# 001-top.net
KiCad netlist of a schematic drawn in EAGLE
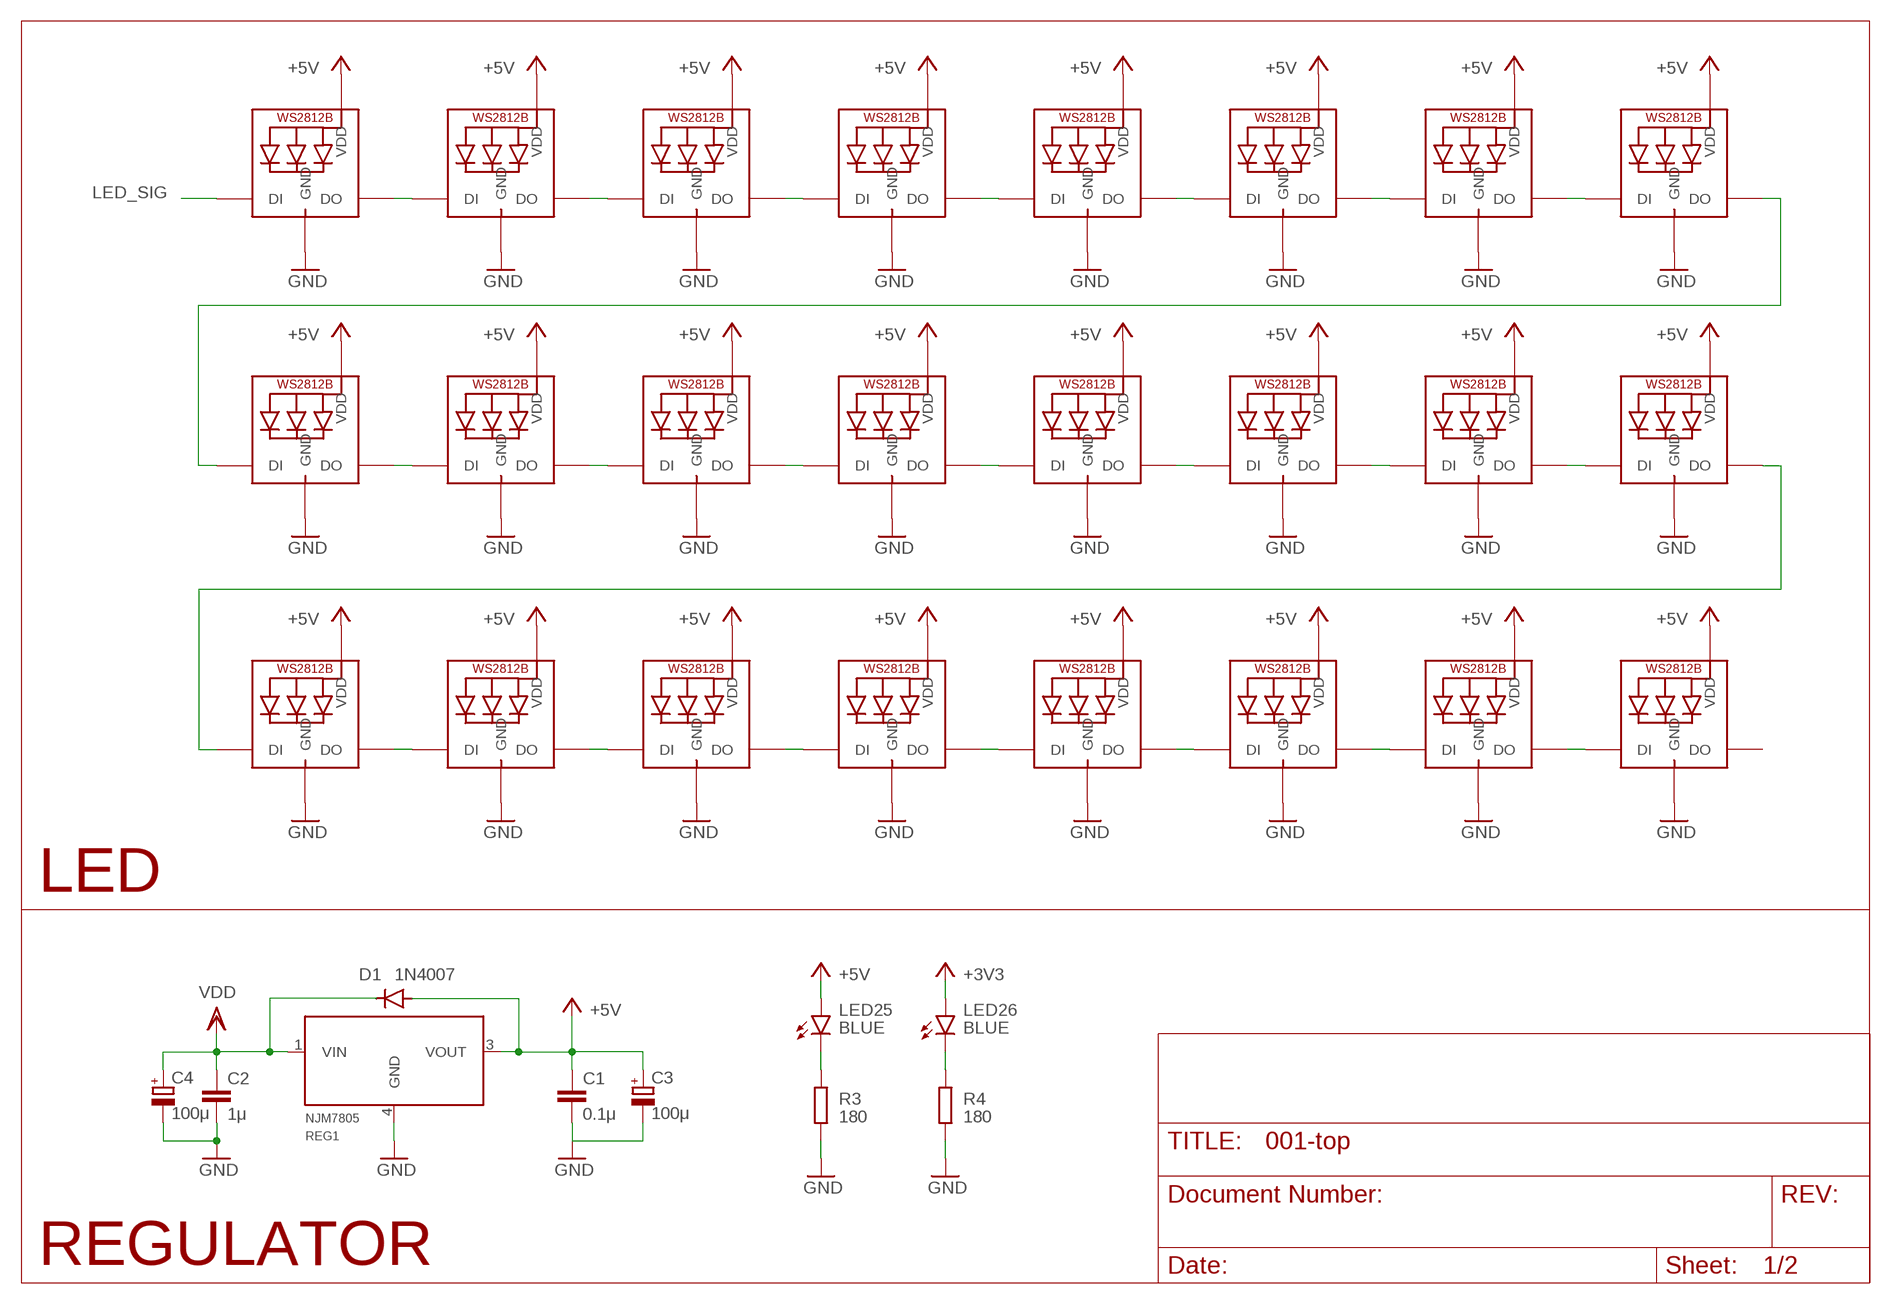
[diagram p0: schematic, sheet 1]
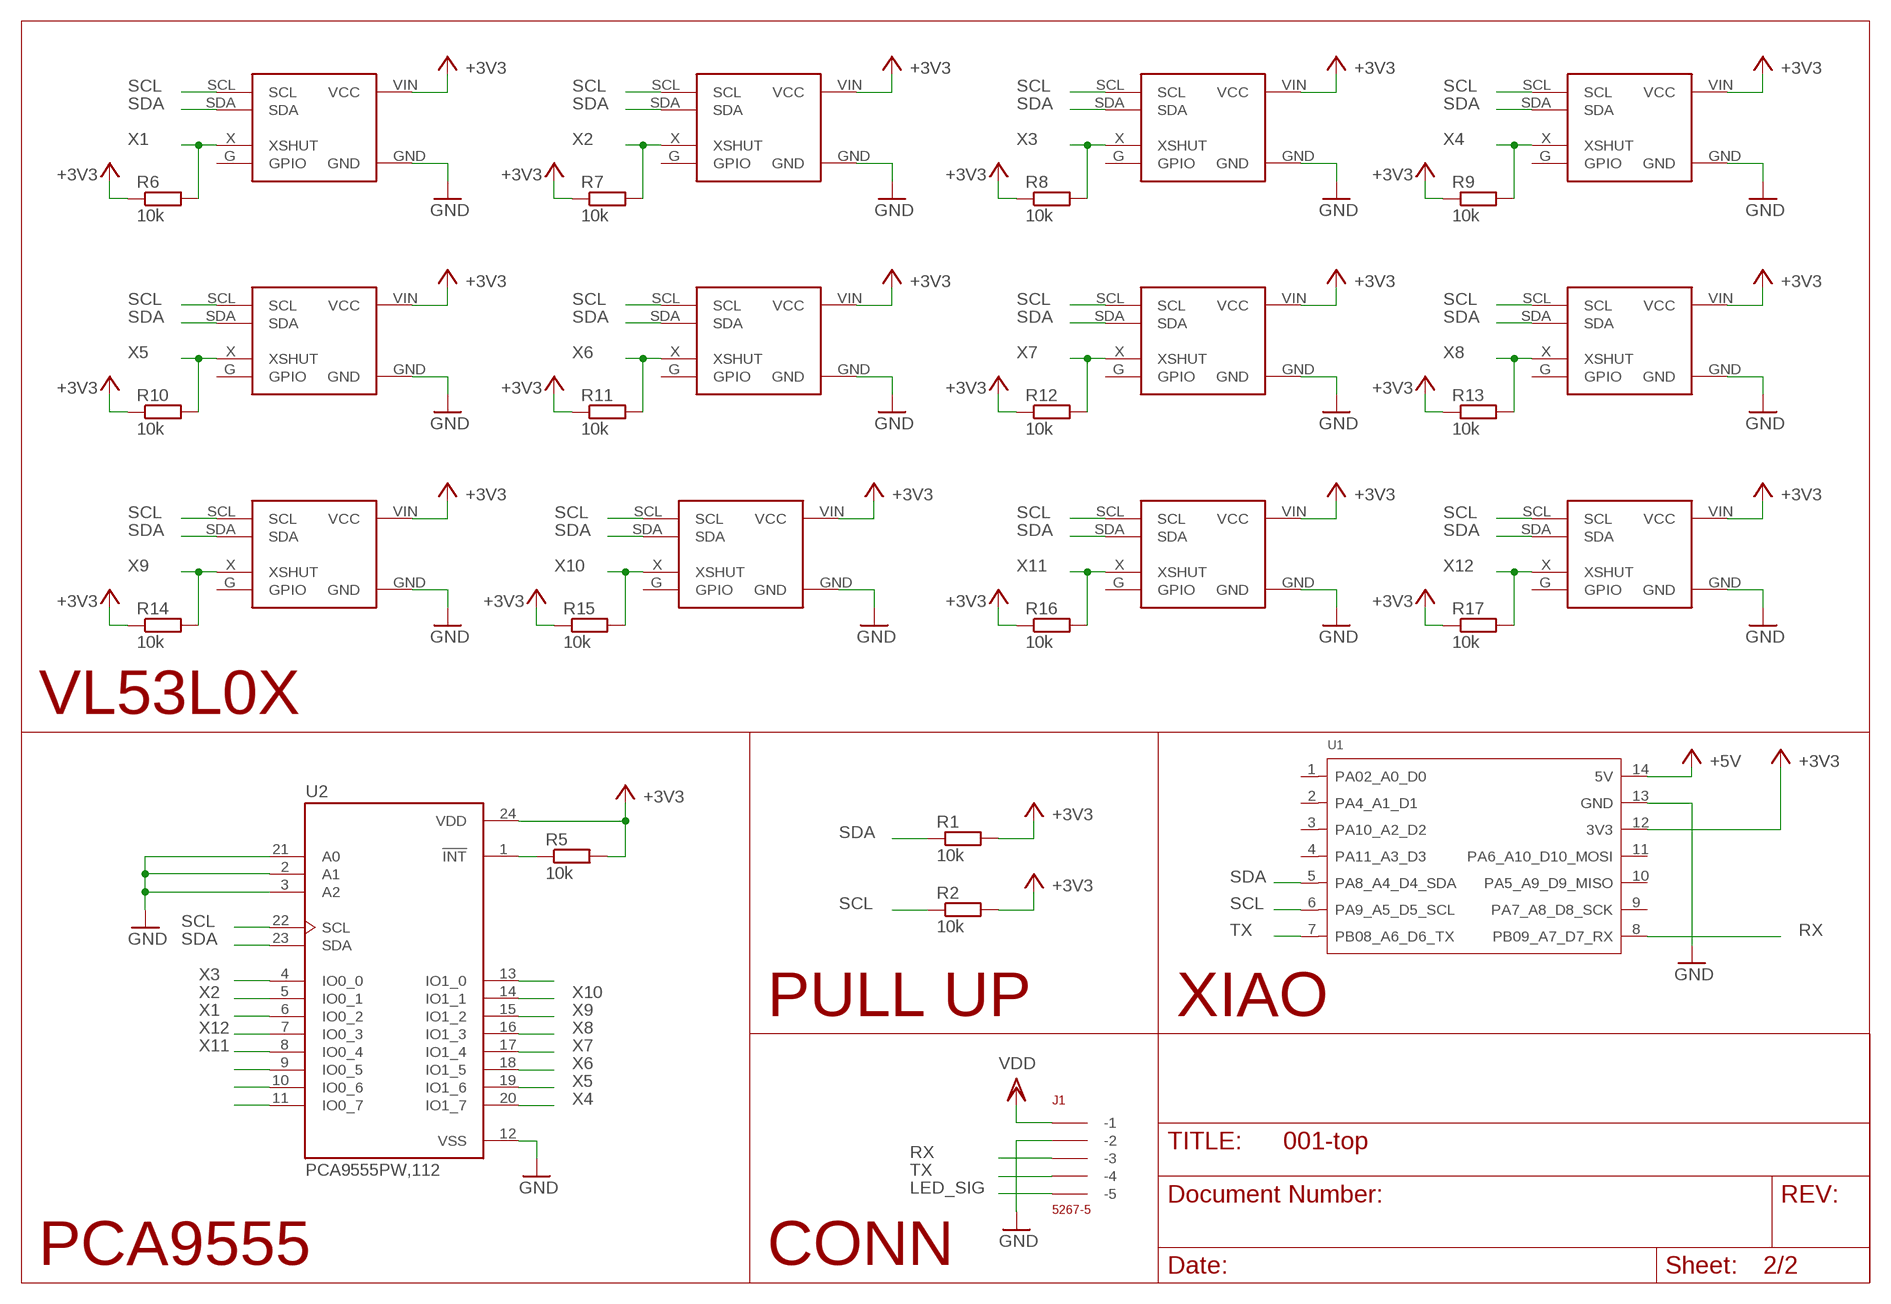
[diagram p1: schematic, sheet 2]

(export (version "E")
  (design (tool "Eeschema 10.0.6"))
  (components
    (comp (ref "C1")
      (value "0.1μ")
      (footprint "eagle-import:C0402")
      (libsource (lib "eagle-import") (part "C-EUC0402"))
    )
    (comp (ref "C2")
      (value "1μ")
      (footprint "eagle-import:C0402")
      (libsource (lib "eagle-import") (part "C-EUC0402"))
    )
    (comp (ref "C3")
      (value "100μ")
      (footprint "eagle-import:153CLV-0505")
      (libsource (lib "eagle-import") (part "CPOL-EU153CLV-0505"))
    )
    (comp (ref "C4")
      (value "100μ")
      (footprint "eagle-import:153CLV-0505")
      (libsource (lib "eagle-import") (part "CPOL-EU153CLV-0505"))
    )
    (comp (ref "D1")
      (value "1N4007")
      (footprint "eagle-import:SMA-DO214AC")
      (libsource (lib "eagle-import") (part "GF1"))
    )
    (comp (ref "LED1")
      (value "WS2812B_5050N")
      (footprint "eagle-import:WS2812B-NARROW")
      (libsource (lib "eagle-import") (part "WS2812B_5050N"))
    )
    (comp (ref "LED2")
      (value "WS2812B_5050N")
      (footprint "eagle-import:WS2812B-NARROW")
      (libsource (lib "eagle-import") (part "WS2812B_5050N"))
    )
    (comp (ref "LED3")
      (value "WS2812B_5050N")
      (footprint "eagle-import:WS2812B-NARROW")
      (libsource (lib "eagle-import") (part "WS2812B_5050N"))
    )
    (comp (ref "LED4")
      (value "WS2812B_5050N")
      (footprint "eagle-import:WS2812B-NARROW")
      (libsource (lib "eagle-import") (part "WS2812B_5050N"))
    )
    (comp (ref "LED5")
      (value "WS2812B_5050N")
      (footprint "eagle-import:WS2812B-NARROW")
      (libsource (lib "eagle-import") (part "WS2812B_5050N"))
    )
    (comp (ref "LED6")
      (value "WS2812B_5050N")
      (footprint "eagle-import:WS2812B-NARROW")
      (libsource (lib "eagle-import") (part "WS2812B_5050N"))
    )
    (comp (ref "LED7")
      (value "WS2812B_5050N")
      (footprint "eagle-import:WS2812B-NARROW")
      (libsource (lib "eagle-import") (part "WS2812B_5050N"))
    )
    (comp (ref "LED8")
      (value "WS2812B_5050N")
      (footprint "eagle-import:WS2812B-NARROW")
      (libsource (lib "eagle-import") (part "WS2812B_5050N"))
    )
    (comp (ref "LED9")
      (value "WS2812B_5050N")
      (footprint "eagle-import:WS2812B-NARROW")
      (libsource (lib "eagle-import") (part "WS2812B_5050N"))
    )
    (comp (ref "LED10")
      (value "WS2812B_5050N")
      (footprint "eagle-import:WS2812B-NARROW")
      (libsource (lib "eagle-import") (part "WS2812B_5050N"))
    )
    (comp (ref "LED11")
      (value "WS2812B_5050N")
      (footprint "eagle-import:WS2812B-NARROW")
      (libsource (lib "eagle-import") (part "WS2812B_5050N"))
    )
    (comp (ref "LED12")
      (value "WS2812B_5050N")
      (footprint "eagle-import:WS2812B-NARROW")
      (libsource (lib "eagle-import") (part "WS2812B_5050N"))
    )
    (comp (ref "LED13")
      (value "WS2812B_5050N")
      (footprint "eagle-import:WS2812B-NARROW")
      (libsource (lib "eagle-import") (part "WS2812B_5050N"))
    )
    (comp (ref "LED14")
      (value "WS2812B_5050N")
      (footprint "eagle-import:WS2812B-NARROW")
      (libsource (lib "eagle-import") (part "WS2812B_5050N"))
    )
    (comp (ref "LED15")
      (value "WS2812B_5050N")
      (footprint "eagle-import:WS2812B-NARROW")
      (libsource (lib "eagle-import") (part "WS2812B_5050N"))
    )
    (comp (ref "LED16")
      (value "WS2812B_5050N")
      (footprint "eagle-import:WS2812B-NARROW")
      (libsource (lib "eagle-import") (part "WS2812B_5050N"))
    )
    (comp (ref "LED17")
      (value "WS2812B_5050N")
      (footprint "eagle-import:WS2812B-NARROW")
      (libsource (lib "eagle-import") (part "WS2812B_5050N"))
    )
    (comp (ref "LED18")
      (value "WS2812B_5050N")
      (footprint "eagle-import:WS2812B-NARROW")
      (libsource (lib "eagle-import") (part "WS2812B_5050N"))
    )
    (comp (ref "LED19")
      (value "WS2812B_5050N")
      (footprint "eagle-import:WS2812B-NARROW")
      (libsource (lib "eagle-import") (part "WS2812B_5050N"))
    )
    (comp (ref "LED20")
      (value "WS2812B_5050N")
      (footprint "eagle-import:WS2812B-NARROW")
      (libsource (lib "eagle-import") (part "WS2812B_5050N"))
    )
    (comp (ref "LED21")
      (value "WS2812B_5050N")
      (footprint "eagle-import:WS2812B-NARROW")
      (libsource (lib "eagle-import") (part "WS2812B_5050N"))
    )
    (comp (ref "LED22")
      (value "WS2812B_5050N")
      (footprint "eagle-import:WS2812B-NARROW")
      (libsource (lib "eagle-import") (part "WS2812B_5050N"))
    )
    (comp (ref "LED23")
      (value "WS2812B_5050N")
      (footprint "eagle-import:WS2812B-NARROW")
      (libsource (lib "eagle-import") (part "WS2812B_5050N"))
    )
    (comp (ref "LED24")
      (value "WS2812B_5050N")
      (footprint "eagle-import:WS2812B-NARROW")
      (libsource (lib "eagle-import") (part "WS2812B_5050N"))
    )
    (comp (ref "LED25")
      (value "BLUE")
      (footprint "eagle-import:SML0603")
      (libsource (lib "eagle-import") (part "LEDSML0603"))
    )
    (comp (ref "LED26")
      (value "BLUE")
      (footprint "eagle-import:SML0603")
      (libsource (lib "eagle-import") (part "LEDSML0603"))
    )
    (comp (ref "R3")
      (value "180")
      (footprint "eagle-import:R0402")
      (libsource (lib "eagle-import") (part "R-EU_R0402"))
    )
    (comp (ref "R4")
      (value "180")
      (footprint "eagle-import:R0402")
      (libsource (lib "eagle-import") (part "R-EU_R0402"))
    )
    (comp (ref "REG1")
      (value "NJM7805")
      (footprint "eagle-import:MYPARTS_D-PAK_TO252AA")
      (libsource (lib "eagle-import") (part "MYPARTS_NJM7800S-REGULATOR"))
    )
    (comp (ref "J1")
      (value "5267-5")
      (footprint "eagle-import:5267-5")
      (libsource (lib "eagle-import") (part "5267-5"))
    )
    (comp (ref "R1")
      (value "10k")
      (footprint "eagle-import:R0402")
      (libsource (lib "eagle-import") (part "R-EU_R0402"))
    )
    (comp (ref "R2")
      (value "10k")
      (footprint "eagle-import:R0402")
      (libsource (lib "eagle-import") (part "R-EU_R0402"))
    )
    (comp (ref "R5")
      (value "10k")
      (footprint "eagle-import:R0402")
      (libsource (lib "eagle-import") (part "R-EU_R0402"))
    )
    (comp (ref "R6")
      (value "10k")
      (footprint "eagle-import:R0402")
      (libsource (lib "eagle-import") (part "R-EU_R0402"))
    )
    (comp (ref "R7")
      (value "10k")
      (footprint "eagle-import:R0402")
      (libsource (lib "eagle-import") (part "R-EU_R0402"))
    )
    (comp (ref "R8")
      (value "10k")
      (footprint "eagle-import:R0402")
      (libsource (lib "eagle-import") (part "R-EU_R0402"))
    )
    (comp (ref "R9")
      (value "10k")
      (footprint "eagle-import:R0402")
      (libsource (lib "eagle-import") (part "R-EU_R0402"))
    )
    (comp (ref "R10")
      (value "10k")
      (footprint "eagle-import:R0402")
      (libsource (lib "eagle-import") (part "R-EU_R0402"))
    )
    (comp (ref "R11")
      (value "10k")
      (footprint "eagle-import:R0402")
      (libsource (lib "eagle-import") (part "R-EU_R0402"))
    )
    (comp (ref "R12")
      (value "10k")
      (footprint "eagle-import:R0402")
      (libsource (lib "eagle-import") (part "R-EU_R0402"))
    )
    (comp (ref "R13")
      (value "10k")
      (footprint "eagle-import:R0402")
      (libsource (lib "eagle-import") (part "R-EU_R0402"))
    )
    (comp (ref "R14")
      (value "10k")
      (footprint "eagle-import:R0402")
      (libsource (lib "eagle-import") (part "R-EU_R0402"))
    )
    (comp (ref "R15")
      (value "10k")
      (footprint "eagle-import:R0402")
      (libsource (lib "eagle-import") (part "R-EU_R0402"))
    )
    (comp (ref "R16")
      (value "10k")
      (footprint "eagle-import:R0402")
      (libsource (lib "eagle-import") (part "R-EU_R0402"))
    )
    (comp (ref "R17")
      (value "10k")
      (footprint "eagle-import:R0402")
      (libsource (lib "eagle-import") (part "R-EU_R0402"))
    )
    (comp (ref "U1")
      (value "MOUDLE-SEEEDUINO-XIAO")
      (footprint "eagle-import:MOUDLE14P-2.54-21X17.8MM")
      (libsource (lib "eagle-import") (part "MOUDLE-SEEEDUINO-XIAO"))
    )
    (comp (ref "U2")
      (value "PCA9555PW,112")
      (footprint "eagle-import:SOP65P640X110-24N")
      (fields (field (name "MF") "NXP Semiconductors"))
      (libsource (lib "eagle-import") (part "PCA9555PW,112"))
    )
    (comp (ref "VL1")
      (value "VL53L0X")
      (footprint "eagle-import:1X04")
      (libsource (lib "eagle-import") (part "VL53L0X"))
    )
    (comp (ref "VL2")
      (value "VL53L0X")
      (footprint "eagle-import:1X04")
      (libsource (lib "eagle-import") (part "VL53L0X"))
    )
    (comp (ref "VL3")
      (value "VL53L0X")
      (footprint "eagle-import:1X04")
      (libsource (lib "eagle-import") (part "VL53L0X"))
    )
    (comp (ref "VL4")
      (value "VL53L0X")
      (footprint "eagle-import:1X04")
      (libsource (lib "eagle-import") (part "VL53L0X"))
    )
    (comp (ref "VL5")
      (value "VL53L0X")
      (footprint "eagle-import:1X04")
      (libsource (lib "eagle-import") (part "VL53L0X"))
    )
    (comp (ref "VL6")
      (value "VL53L0X")
      (footprint "eagle-import:1X04")
      (libsource (lib "eagle-import") (part "VL53L0X"))
    )
    (comp (ref "VL7")
      (value "VL53L0X")
      (footprint "eagle-import:1X04")
      (libsource (lib "eagle-import") (part "VL53L0X"))
    )
    (comp (ref "VL8")
      (value "VL53L0X")
      (footprint "eagle-import:1X04")
      (libsource (lib "eagle-import") (part "VL53L0X"))
    )
    (comp (ref "VL9")
      (value "VL53L0X")
      (footprint "eagle-import:1X04")
      (libsource (lib "eagle-import") (part "VL53L0X"))
    )
    (comp (ref "VL10")
      (value "VL53L0X")
      (footprint "eagle-import:1X04")
      (libsource (lib "eagle-import") (part "VL53L0X"))
    )
    (comp (ref "VL11")
      (value "VL53L0X")
      (footprint "eagle-import:1X04")
      (libsource (lib "eagle-import") (part "VL53L0X"))
    )
    (comp (ref "VL12")
      (value "VL53L0X")
      (footprint "eagle-import:1X04")
      (libsource (lib "eagle-import") (part "VL53L0X"))
    )
  )
  (nets
    (net (code "1") (name "+3V3") (class "Default")
      (node (ref "LED26") (pin "A") (pinfunction "A_A") (pintype "passive"))
      (node (ref "R1") (pin "2") (pinfunction "2_2") (pintype "passive"))
      (node (ref "R10") (pin "1") (pinfunction "1_1") (pintype "passive"))
      (node (ref "R11") (pin "1") (pinfunction "1_1") (pintype "passive"))
      (node (ref "R12") (pin "1") (pinfunction "1_1") (pintype "passive"))
      (node (ref "R13") (pin "1") (pinfunction "1_1") (pintype "passive"))
      (node (ref "R14") (pin "1") (pinfunction "1_1") (pintype "passive"))
      (node (ref "R15") (pin "1") (pinfunction "1_1") (pintype "passive"))
      (node (ref "R16") (pin "1") (pinfunction "1_1") (pintype "passive"))
      (node (ref "R17") (pin "1") (pinfunction "1_1") (pintype "passive"))
      (node (ref "R2") (pin "2") (pinfunction "2_2") (pintype "passive"))
      (node (ref "R5") (pin "2") (pinfunction "2_2") (pintype "passive"))
      (node (ref "R6") (pin "1") (pinfunction "1_1") (pintype "passive"))
      (node (ref "R7") (pin "1") (pinfunction "1_1") (pintype "passive"))
      (node (ref "R8") (pin "1") (pinfunction "1_1") (pintype "passive"))
      (node (ref "R9") (pin "1") (pinfunction "1_1") (pintype "passive"))
      (node (ref "U1") (pin "12") (pinfunction "3V3_12") (pintype "bidirectional"))
      (node (ref "U2") (pin "24") (pinfunction "VDD_24") (pintype "power_in"))
      (node (ref "VL1") (pin "VIN") (pinfunction "VCC_VIN") (pintype "bidirectional"))
      (node (ref "VL10") (pin "VIN") (pinfunction "VCC_VIN") (pintype "bidirectional"))
      (node (ref "VL11") (pin "VIN") (pinfunction "VCC_VIN") (pintype "bidirectional"))
      (node (ref "VL12") (pin "VIN") (pinfunction "VCC_VIN") (pintype "bidirectional"))
      (node (ref "VL2") (pin "VIN") (pinfunction "VCC_VIN") (pintype "bidirectional"))
      (node (ref "VL3") (pin "VIN") (pinfunction "VCC_VIN") (pintype "bidirectional"))
      (node (ref "VL4") (pin "VIN") (pinfunction "VCC_VIN") (pintype "bidirectional"))
      (node (ref "VL5") (pin "VIN") (pinfunction "VCC_VIN") (pintype "bidirectional"))
      (node (ref "VL6") (pin "VIN") (pinfunction "VCC_VIN") (pintype "bidirectional"))
      (node (ref "VL7") (pin "VIN") (pinfunction "VCC_VIN") (pintype "bidirectional"))
      (node (ref "VL8") (pin "VIN") (pinfunction "VCC_VIN") (pintype "bidirectional"))
      (node (ref "VL9") (pin "VIN") (pinfunction "VCC_VIN") (pintype "bidirectional"))
    )
    (net (code "2") (name "+5V") (class "Default")
      (node (ref "C1") (pin "1") (pinfunction "1_1") (pintype "passive"))
      (node (ref "C3") (pin "+") (pinfunction "+_+") (pintype "passive"))
      (node (ref "D1") (pin "A") (pinfunction "A_A") (pintype "passive"))
      (node (ref "LED1") (pin "1-VDD") (pinfunction "VDD_1-VDD") (pintype "power_in"))
      (node (ref "LED10") (pin "1-VDD") (pinfunction "VDD_1-VDD") (pintype "power_in"))
      (node (ref "LED11") (pin "1-VDD") (pinfunction "VDD_1-VDD") (pintype "power_in"))
      (node (ref "LED12") (pin "1-VDD") (pinfunction "VDD_1-VDD") (pintype "power_in"))
      (node (ref "LED13") (pin "1-VDD") (pinfunction "VDD_1-VDD") (pintype "power_in"))
      (node (ref "LED14") (pin "1-VDD") (pinfunction "VDD_1-VDD") (pintype "power_in"))
      (node (ref "LED15") (pin "1-VDD") (pinfunction "VDD_1-VDD") (pintype "power_in"))
      (node (ref "LED16") (pin "1-VDD") (pinfunction "VDD_1-VDD") (pintype "power_in"))
      (node (ref "LED17") (pin "1-VDD") (pinfunction "VDD_1-VDD") (pintype "power_in"))
      (node (ref "LED18") (pin "1-VDD") (pinfunction "VDD_1-VDD") (pintype "power_in"))
      (node (ref "LED19") (pin "1-VDD") (pinfunction "VDD_1-VDD") (pintype "power_in"))
      (node (ref "LED2") (pin "1-VDD") (pinfunction "VDD_1-VDD") (pintype "power_in"))
      (node (ref "LED20") (pin "1-VDD") (pinfunction "VDD_1-VDD") (pintype "power_in"))
      (node (ref "LED21") (pin "1-VDD") (pinfunction "VDD_1-VDD") (pintype "power_in"))
      (node (ref "LED22") (pin "1-VDD") (pinfunction "VDD_1-VDD") (pintype "power_in"))
      (node (ref "LED23") (pin "1-VDD") (pinfunction "VDD_1-VDD") (pintype "power_in"))
      (node (ref "LED24") (pin "1-VDD") (pinfunction "VDD_1-VDD") (pintype "power_in"))
      (node (ref "LED25") (pin "A") (pinfunction "A_A") (pintype "passive"))
      (node (ref "LED3") (pin "1-VDD") (pinfunction "VDD_1-VDD") (pintype "power_in"))
      (node (ref "LED4") (pin "1-VDD") (pinfunction "VDD_1-VDD") (pintype "power_in"))
      (node (ref "LED5") (pin "1-VDD") (pinfunction "VDD_1-VDD") (pintype "power_in"))
      (node (ref "LED6") (pin "1-VDD") (pinfunction "VDD_1-VDD") (pintype "power_in"))
      (node (ref "LED7") (pin "1-VDD") (pinfunction "VDD_1-VDD") (pintype "power_in"))
      (node (ref "LED8") (pin "1-VDD") (pinfunction "VDD_1-VDD") (pintype "power_in"))
      (node (ref "LED9") (pin "1-VDD") (pinfunction "VDD_1-VDD") (pintype "power_in"))
      (node (ref "REG1") (pin "3") (pinfunction "VOUT_3") (pintype "passive"))
      (node (ref "U1") (pin "14") (pinfunction "5V_14") (pintype "bidirectional"))
    )
    (net (code "3") (name "GND") (class "Default")
      (node (ref "C1") (pin "2") (pinfunction "2_2") (pintype "passive"))
      (node (ref "C2") (pin "2") (pinfunction "2_2") (pintype "passive"))
      (node (ref "C3") (pin "-") (pinfunction "-_-") (pintype "passive"))
      (node (ref "C4") (pin "-") (pinfunction "-_-") (pintype "passive"))
      (node (ref "J1") (pin "P$2") (pinfunction "-2_P$2") (pintype "bidirectional"))
      (node (ref "LED1") (pin "3-GND") (pinfunction "GND_3-GND") (pintype "power_in"))
      (node (ref "LED10") (pin "3-GND") (pinfunction "GND_3-GND") (pintype "power_in"))
      (node (ref "LED11") (pin "3-GND") (pinfunction "GND_3-GND") (pintype "power_in"))
      (node (ref "LED12") (pin "3-GND") (pinfunction "GND_3-GND") (pintype "power_in"))
      (node (ref "LED13") (pin "3-GND") (pinfunction "GND_3-GND") (pintype "power_in"))
      (node (ref "LED14") (pin "3-GND") (pinfunction "GND_3-GND") (pintype "power_in"))
      (node (ref "LED15") (pin "3-GND") (pinfunction "GND_3-GND") (pintype "power_in"))
      (node (ref "LED16") (pin "3-GND") (pinfunction "GND_3-GND") (pintype "power_in"))
      (node (ref "LED17") (pin "3-GND") (pinfunction "GND_3-GND") (pintype "power_in"))
      (node (ref "LED18") (pin "3-GND") (pinfunction "GND_3-GND") (pintype "power_in"))
      (node (ref "LED19") (pin "3-GND") (pinfunction "GND_3-GND") (pintype "power_in"))
      (node (ref "LED2") (pin "3-GND") (pinfunction "GND_3-GND") (pintype "power_in"))
      (node (ref "LED20") (pin "3-GND") (pinfunction "GND_3-GND") (pintype "power_in"))
      (node (ref "LED21") (pin "3-GND") (pinfunction "GND_3-GND") (pintype "power_in"))
      (node (ref "LED22") (pin "3-GND") (pinfunction "GND_3-GND") (pintype "power_in"))
      (node (ref "LED23") (pin "3-GND") (pinfunction "GND_3-GND") (pintype "power_in"))
      (node (ref "LED24") (pin "3-GND") (pinfunction "GND_3-GND") (pintype "power_in"))
      (node (ref "LED3") (pin "3-GND") (pinfunction "GND_3-GND") (pintype "power_in"))
      (node (ref "LED4") (pin "3-GND") (pinfunction "GND_3-GND") (pintype "power_in"))
      (node (ref "LED5") (pin "3-GND") (pinfunction "GND_3-GND") (pintype "power_in"))
      (node (ref "LED6") (pin "3-GND") (pinfunction "GND_3-GND") (pintype "power_in"))
      (node (ref "LED7") (pin "3-GND") (pinfunction "GND_3-GND") (pintype "power_in"))
      (node (ref "LED8") (pin "3-GND") (pinfunction "GND_3-GND") (pintype "power_in"))
      (node (ref "LED9") (pin "3-GND") (pinfunction "GND_3-GND") (pintype "power_in"))
      (node (ref "R3") (pin "2") (pinfunction "2_2") (pintype "passive"))
      (node (ref "R4") (pin "2") (pinfunction "2_2") (pintype "passive"))
      (node (ref "REG1") (pin "4") (pinfunction "GND_4") (pintype "passive"))
      (node (ref "U1") (pin "13") (pinfunction "GND_13") (pintype "bidirectional"))
      (node (ref "U2") (pin "12") (pinfunction "VSS_12") (pintype "power_in"))
      (node (ref "U2") (pin "2") (pinfunction "A1_2") (pintype "input"))
      (node (ref "U2") (pin "21") (pinfunction "A0_21") (pintype "input"))
      (node (ref "U2") (pin "3") (pinfunction "A2_3") (pintype "input"))
      (node (ref "VL1") (pin "GND") (pinfunction "GND_GND") (pintype "bidirectional"))
      (node (ref "VL10") (pin "GND") (pinfunction "GND_GND") (pintype "bidirectional"))
      (node (ref "VL11") (pin "GND") (pinfunction "GND_GND") (pintype "bidirectional"))
      (node (ref "VL12") (pin "GND") (pinfunction "GND_GND") (pintype "bidirectional"))
      (node (ref "VL2") (pin "GND") (pinfunction "GND_GND") (pintype "bidirectional"))
      (node (ref "VL3") (pin "GND") (pinfunction "GND_GND") (pintype "bidirectional"))
      (node (ref "VL4") (pin "GND") (pinfunction "GND_GND") (pintype "bidirectional"))
      (node (ref "VL5") (pin "GND") (pinfunction "GND_GND") (pintype "bidirectional"))
      (node (ref "VL6") (pin "GND") (pinfunction "GND_GND") (pintype "bidirectional"))
      (node (ref "VL7") (pin "GND") (pinfunction "GND_GND") (pintype "bidirectional"))
      (node (ref "VL8") (pin "GND") (pinfunction "GND_GND") (pintype "bidirectional"))
      (node (ref "VL9") (pin "GND") (pinfunction "GND_GND") (pintype "bidirectional"))
    )
    (net (code "4") (name "LED_SIG") (class "Default")
      (node (ref "J1") (pin "P$5") (pinfunction "-5_P$5") (pintype "bidirectional"))
      (node (ref "LED1") (pin "4-DIN") (pinfunction "DI_4-DIN") (pintype "input"))
    )
    (net (code "5") (name "Net-(LED1-DO)") (class "Default")
      (node (ref "LED1") (pin "2-DOUT") (pinfunction "DO_2-DOUT") (pintype "output"))
      (node (ref "LED2") (pin "4-DIN") (pinfunction "DI_4-DIN") (pintype "input"))
    )
    (net (code "6") (name "Net-(LED2-DO)") (class "Default")
      (node (ref "LED2") (pin "2-DOUT") (pinfunction "DO_2-DOUT") (pintype "output"))
      (node (ref "LED3") (pin "4-DIN") (pinfunction "DI_4-DIN") (pintype "input"))
    )
    (net (code "7") (name "Net-(LED3-DO)") (class "Default")
      (node (ref "LED3") (pin "2-DOUT") (pinfunction "DO_2-DOUT") (pintype "output"))
      (node (ref "LED4") (pin "4-DIN") (pinfunction "DI_4-DIN") (pintype "input"))
    )
    (net (code "8") (name "Net-(LED4-DO)") (class "Default")
      (node (ref "LED4") (pin "2-DOUT") (pinfunction "DO_2-DOUT") (pintype "output"))
      (node (ref "LED5") (pin "4-DIN") (pinfunction "DI_4-DIN") (pintype "input"))
    )
    (net (code "9") (name "Net-(LED5-DO)") (class "Default")
      (node (ref "LED5") (pin "2-DOUT") (pinfunction "DO_2-DOUT") (pintype "output"))
      (node (ref "LED6") (pin "4-DIN") (pinfunction "DI_4-DIN") (pintype "input"))
    )
    (net (code "10") (name "Net-(LED6-DO)") (class "Default")
      (node (ref "LED6") (pin "2-DOUT") (pinfunction "DO_2-DOUT") (pintype "output"))
      (node (ref "LED7") (pin "4-DIN") (pinfunction "DI_4-DIN") (pintype "input"))
    )
    (net (code "11") (name "Net-(LED7-DO)") (class "Default")
      (node (ref "LED7") (pin "2-DOUT") (pinfunction "DO_2-DOUT") (pintype "output"))
      (node (ref "LED8") (pin "4-DIN") (pinfunction "DI_4-DIN") (pintype "input"))
    )
    (net (code "12") (name "Net-(LED8-DO)") (class "Default")
      (node (ref "LED8") (pin "2-DOUT") (pinfunction "DO_2-DOUT") (pintype "output"))
      (node (ref "LED9") (pin "4-DIN") (pinfunction "DI_4-DIN") (pintype "input"))
    )
    (net (code "13") (name "Net-(LED10-DI)") (class "Default")
      (node (ref "LED10") (pin "4-DIN") (pinfunction "DI_4-DIN") (pintype "input"))
      (node (ref "LED9") (pin "2-DOUT") (pinfunction "DO_2-DOUT") (pintype "output"))
    )
    (net (code "14") (name "Net-(LED10-DO)") (class "Default")
      (node (ref "LED10") (pin "2-DOUT") (pinfunction "DO_2-DOUT") (pintype "output"))
      (node (ref "LED11") (pin "4-DIN") (pinfunction "DI_4-DIN") (pintype "input"))
    )
    (net (code "15") (name "Net-(LED11-DO)") (class "Default")
      (node (ref "LED11") (pin "2-DOUT") (pinfunction "DO_2-DOUT") (pintype "output"))
      (node (ref "LED12") (pin "4-DIN") (pinfunction "DI_4-DIN") (pintype "input"))
    )
    (net (code "16") (name "Net-(LED12-DO)") (class "Default")
      (node (ref "LED12") (pin "2-DOUT") (pinfunction "DO_2-DOUT") (pintype "output"))
      (node (ref "LED13") (pin "4-DIN") (pinfunction "DI_4-DIN") (pintype "input"))
    )
    (net (code "17") (name "Net-(LED13-DO)") (class "Default")
      (node (ref "LED13") (pin "2-DOUT") (pinfunction "DO_2-DOUT") (pintype "output"))
      (node (ref "LED14") (pin "4-DIN") (pinfunction "DI_4-DIN") (pintype "input"))
    )
    (net (code "18") (name "Net-(LED14-DO)") (class "Default")
      (node (ref "LED14") (pin "2-DOUT") (pinfunction "DO_2-DOUT") (pintype "output"))
      (node (ref "LED15") (pin "4-DIN") (pinfunction "DI_4-DIN") (pintype "input"))
    )
    (net (code "19") (name "Net-(LED15-DO)") (class "Default")
      (node (ref "LED15") (pin "2-DOUT") (pinfunction "DO_2-DOUT") (pintype "output"))
      (node (ref "LED16") (pin "4-DIN") (pinfunction "DI_4-DIN") (pintype "input"))
    )
    (net (code "20") (name "Net-(LED16-DO)") (class "Default")
      (node (ref "LED16") (pin "2-DOUT") (pinfunction "DO_2-DOUT") (pintype "output"))
      (node (ref "LED17") (pin "4-DIN") (pinfunction "DI_4-DIN") (pintype "input"))
    )
    (net (code "21") (name "Net-(LED17-DO)") (class "Default")
      (node (ref "LED17") (pin "2-DOUT") (pinfunction "DO_2-DOUT") (pintype "output"))
      (node (ref "LED18") (pin "4-DIN") (pinfunction "DI_4-DIN") (pintype "input"))
    )
    (net (code "22") (name "Net-(LED18-DO)") (class "Default")
      (node (ref "LED18") (pin "2-DOUT") (pinfunction "DO_2-DOUT") (pintype "output"))
      (node (ref "LED19") (pin "4-DIN") (pinfunction "DI_4-DIN") (pintype "input"))
    )
    (net (code "23") (name "Net-(LED19-DO)") (class "Default")
      (node (ref "LED19") (pin "2-DOUT") (pinfunction "DO_2-DOUT") (pintype "output"))
      (node (ref "LED20") (pin "4-DIN") (pinfunction "DI_4-DIN") (pintype "input"))
    )
    (net (code "24") (name "Net-(LED20-DO)") (class "Default")
      (node (ref "LED20") (pin "2-DOUT") (pinfunction "DO_2-DOUT") (pintype "output"))
      (node (ref "LED21") (pin "4-DIN") (pinfunction "DI_4-DIN") (pintype "input"))
    )
    (net (code "25") (name "Net-(LED21-DO)") (class "Default")
      (node (ref "LED21") (pin "2-DOUT") (pinfunction "DO_2-DOUT") (pintype "output"))
      (node (ref "LED22") (pin "4-DIN") (pinfunction "DI_4-DIN") (pintype "input"))
    )
    (net (code "26") (name "Net-(LED22-DO)") (class "Default")
      (node (ref "LED22") (pin "2-DOUT") (pinfunction "DO_2-DOUT") (pintype "output"))
      (node (ref "LED23") (pin "4-DIN") (pinfunction "DI_4-DIN") (pintype "input"))
    )
    (net (code "27") (name "Net-(LED23-DO)") (class "Default")
      (node (ref "LED23") (pin "2-DOUT") (pinfunction "DO_2-DOUT") (pintype "output"))
      (node (ref "LED24") (pin "4-DIN") (pinfunction "DI_4-DIN") (pintype "input"))
    )
    (net (code "28") (name "Net-(LED25-PadC)") (class "Default")
      (node (ref "LED25") (pin "C") (pinfunction "C_C") (pintype "passive"))
      (node (ref "R3") (pin "1") (pinfunction "1_1") (pintype "passive"))
    )
    (net (code "29") (name "Net-(LED26-PadC)") (class "Default")
      (node (ref "LED26") (pin "C") (pinfunction "C_C") (pintype "passive"))
      (node (ref "R4") (pin "1") (pinfunction "1_1") (pintype "passive"))
    )
    (net (code "30") (name "Net-(U2-~{INT})") (class "Default")
      (node (ref "R5") (pin "1") (pinfunction "1_1") (pintype "passive"))
      (node (ref "U2") (pin "1") (pinfunction "~{INT}_1") (pintype "output"))
    )
    (net (code "31") (name "RX") (class "Default")
      (node (ref "J1") (pin "P$3") (pinfunction "-3_P$3") (pintype "bidirectional"))
      (node (ref "U1") (pin "8") (pinfunction "PB09_A7_D7_RX_8") (pintype "bidirectional"))
    )
    (net (code "32") (name "SCL") (class "Default")
      (node (ref "R2") (pin "1") (pinfunction "1_1") (pintype "passive"))
      (node (ref "U1") (pin "6") (pinfunction "PA9_A5_D5_SCL_6") (pintype "bidirectional"))
      (node (ref "U2") (pin "22") (pinfunction "SCL_22") (pintype "input"))
      (node (ref "VL1") (pin "SCL") (pinfunction "SCL_SCL") (pintype "bidirectional"))
      (node (ref "VL10") (pin "SCL") (pinfunction "SCL_SCL") (pintype "bidirectional"))
      (node (ref "VL11") (pin "SCL") (pinfunction "SCL_SCL") (pintype "bidirectional"))
      (node (ref "VL12") (pin "SCL") (pinfunction "SCL_SCL") (pintype "bidirectional"))
      (node (ref "VL2") (pin "SCL") (pinfunction "SCL_SCL") (pintype "bidirectional"))
      (node (ref "VL3") (pin "SCL") (pinfunction "SCL_SCL") (pintype "bidirectional"))
      (node (ref "VL4") (pin "SCL") (pinfunction "SCL_SCL") (pintype "bidirectional"))
      (node (ref "VL5") (pin "SCL") (pinfunction "SCL_SCL") (pintype "bidirectional"))
      (node (ref "VL6") (pin "SCL") (pinfunction "SCL_SCL") (pintype "bidirectional"))
      (node (ref "VL7") (pin "SCL") (pinfunction "SCL_SCL") (pintype "bidirectional"))
      (node (ref "VL8") (pin "SCL") (pinfunction "SCL_SCL") (pintype "bidirectional"))
      (node (ref "VL9") (pin "SCL") (pinfunction "SCL_SCL") (pintype "bidirectional"))
    )
    (net (code "33") (name "SDA") (class "Default")
      (node (ref "R1") (pin "1") (pinfunction "1_1") (pintype "passive"))
      (node (ref "U1") (pin "5") (pinfunction "PA8_A4_D4_SDA_5") (pintype "bidirectional"))
      (node (ref "U2") (pin "23") (pinfunction "SDA_23") (pintype "bidirectional"))
      (node (ref "VL1") (pin "SDA") (pinfunction "SDA_SDA") (pintype "bidirectional"))
      (node (ref "VL10") (pin "SDA") (pinfunction "SDA_SDA") (pintype "bidirectional"))
      (node (ref "VL11") (pin "SDA") (pinfunction "SDA_SDA") (pintype "bidirectional"))
      (node (ref "VL12") (pin "SDA") (pinfunction "SDA_SDA") (pintype "bidirectional"))
      (node (ref "VL2") (pin "SDA") (pinfunction "SDA_SDA") (pintype "bidirectional"))
      (node (ref "VL3") (pin "SDA") (pinfunction "SDA_SDA") (pintype "bidirectional"))
      (node (ref "VL4") (pin "SDA") (pinfunction "SDA_SDA") (pintype "bidirectional"))
      (node (ref "VL5") (pin "SDA") (pinfunction "SDA_SDA") (pintype "bidirectional"))
      (node (ref "VL6") (pin "SDA") (pinfunction "SDA_SDA") (pintype "bidirectional"))
      (node (ref "VL7") (pin "SDA") (pinfunction "SDA_SDA") (pintype "bidirectional"))
      (node (ref "VL8") (pin "SDA") (pinfunction "SDA_SDA") (pintype "bidirectional"))
      (node (ref "VL9") (pin "SDA") (pinfunction "SDA_SDA") (pintype "bidirectional"))
    )
    (net (code "34") (name "TX") (class "Default")
      (node (ref "J1") (pin "P$4") (pinfunction "-4_P$4") (pintype "bidirectional"))
      (node (ref "U1") (pin "7") (pinfunction "PB08_A6_D6_TX_7") (pintype "bidirectional"))
    )
    (net (code "35") (name "VDD") (class "Default")
      (node (ref "C2") (pin "1") (pinfunction "1_1") (pintype "passive"))
      (node (ref "C4") (pin "+") (pinfunction "+_+") (pintype "passive"))
      (node (ref "D1") (pin "K") (pinfunction "C_K") (pintype "passive"))
      (node (ref "J1") (pin "P$1") (pinfunction "-1_P$1") (pintype "bidirectional"))
      (node (ref "REG1") (pin "1") (pinfunction "VIN_1") (pintype "passive"))
    )
    (net (code "36") (name "X1") (class "Default")
      (node (ref "R6") (pin "2") (pinfunction "2_2") (pintype "passive"))
      (node (ref "U2") (pin "6") (pinfunction "IO0_2_6") (pintype "bidirectional"))
      (node (ref "VL1") (pin "X") (pinfunction "XSHUT_X") (pintype "bidirectional"))
    )
    (net (code "37") (name "X2") (class "Default")
      (node (ref "R7") (pin "2") (pinfunction "2_2") (pintype "passive"))
      (node (ref "U2") (pin "5") (pinfunction "IO0_1_5") (pintype "bidirectional"))
      (node (ref "VL2") (pin "X") (pinfunction "XSHUT_X") (pintype "bidirectional"))
    )
    (net (code "38") (name "X3") (class "Default")
      (node (ref "R8") (pin "2") (pinfunction "2_2") (pintype "passive"))
      (node (ref "U2") (pin "4") (pinfunction "IO0_0_4") (pintype "bidirectional"))
      (node (ref "VL3") (pin "X") (pinfunction "XSHUT_X") (pintype "bidirectional"))
    )
    (net (code "39") (name "X4") (class "Default")
      (node (ref "R9") (pin "2") (pinfunction "2_2") (pintype "passive"))
      (node (ref "U2") (pin "20") (pinfunction "IO1_7_20") (pintype "bidirectional"))
      (node (ref "VL4") (pin "X") (pinfunction "XSHUT_X") (pintype "bidirectional"))
    )
    (net (code "40") (name "X5") (class "Default")
      (node (ref "R10") (pin "2") (pinfunction "2_2") (pintype "passive"))
      (node (ref "U2") (pin "19") (pinfunction "IO1_6_19") (pintype "bidirectional"))
      (node (ref "VL5") (pin "X") (pinfunction "XSHUT_X") (pintype "bidirectional"))
    )
    (net (code "41") (name "X6") (class "Default")
      (node (ref "R11") (pin "2") (pinfunction "2_2") (pintype "passive"))
      (node (ref "U2") (pin "18") (pinfunction "IO1_5_18") (pintype "bidirectional"))
      (node (ref "VL6") (pin "X") (pinfunction "XSHUT_X") (pintype "bidirectional"))
    )
    (net (code "42") (name "X7") (class "Default")
      (node (ref "R12") (pin "2") (pinfunction "2_2") (pintype "passive"))
      (node (ref "U2") (pin "17") (pinfunction "IO1_4_17") (pintype "bidirectional"))
      (node (ref "VL7") (pin "X") (pinfunction "XSHUT_X") (pintype "bidirectional"))
    )
    (net (code "43") (name "X8") (class "Default")
      (node (ref "R13") (pin "2") (pinfunction "2_2") (pintype "passive"))
      (node (ref "U2") (pin "16") (pinfunction "IO1_3_16") (pintype "bidirectional"))
      (node (ref "VL8") (pin "X") (pinfunction "XSHUT_X") (pintype "bidirectional"))
    )
    (net (code "44") (name "X9") (class "Default")
      (node (ref "R14") (pin "2") (pinfunction "2_2") (pintype "passive"))
      (node (ref "U2") (pin "15") (pinfunction "IO1_2_15") (pintype "bidirectional"))
      (node (ref "VL9") (pin "X") (pinfunction "XSHUT_X") (pintype "bidirectional"))
    )
    (net (code "45") (name "X10") (class "Default")
      (node (ref "R15") (pin "2") (pinfunction "2_2") (pintype "passive"))
      (node (ref "U2") (pin "14") (pinfunction "IO1_1_14") (pintype "bidirectional"))
      (node (ref "VL10") (pin "X") (pinfunction "XSHUT_X") (pintype "bidirectional"))
    )
    (net (code "46") (name "X11") (class "Default")
      (node (ref "R16") (pin "2") (pinfunction "2_2") (pintype "passive"))
      (node (ref "U2") (pin "8") (pinfunction "IO0_4_8") (pintype "bidirectional"))
      (node (ref "VL11") (pin "X") (pinfunction "XSHUT_X") (pintype "bidirectional"))
    )
    (net (code "47") (name "X12") (class "Default")
      (node (ref "R17") (pin "2") (pinfunction "2_2") (pintype "passive"))
      (node (ref "U2") (pin "7") (pinfunction "IO0_3_7") (pintype "bidirectional"))
      (node (ref "VL12") (pin "X") (pinfunction "XSHUT_X") (pintype "bidirectional"))
    )
    (net (code "48") (name "unconnected-(LED24-DO-Pad2-DOUT)") (class "Default")
      (node (ref "LED24") (pin "2-DOUT") (pinfunction "DO_2-DOUT") (pintype "output"))
    )
    (net (code "49") (name "unconnected-(U1-PA02_A0_D0-Pad1)") (class "Default")
      (node (ref "U1") (pin "1") (pinfunction "PA02_A0_D0_1") (pintype "bidirectional"))
    )
    (net (code "50") (name "unconnected-(U1-PA4_A1_D1-Pad2)") (class "Default")
      (node (ref "U1") (pin "2") (pinfunction "PA4_A1_D1_2") (pintype "bidirectional"))
    )
    (net (code "51") (name "unconnected-(U1-PA5_A9_D9_MISO-Pad10)") (class "Default")
      (node (ref "U1") (pin "10") (pinfunction "PA5_A9_D9_MISO_10") (pintype "bidirectional"))
    )
    (net (code "52") (name "unconnected-(U1-PA6_A10_D10_MOSI-Pad11)") (class "Default")
      (node (ref "U1") (pin "11") (pinfunction "PA6_A10_D10_MOSI_11") (pintype "bidirectional"))
    )
    (net (code "53") (name "unconnected-(U1-PA7_A8_D8_SCK-Pad9)") (class "Default")
      (node (ref "U1") (pin "9") (pinfunction "PA7_A8_D8_SCK_9") (pintype "bidirectional"))
    )
    (net (code "54") (name "unconnected-(U1-PA10_A2_D2-Pad3)") (class "Default")
      (node (ref "U1") (pin "3") (pinfunction "PA10_A2_D2_3") (pintype "bidirectional"))
    )
    (net (code "55") (name "unconnected-(U1-PA11_A3_D3-Pad4)") (class "Default")
      (node (ref "U1") (pin "4") (pinfunction "PA11_A3_D3_4") (pintype "bidirectional"))
    )
    (net (code "56") (name "unconnected-(U2-IO0_5-Pad9)") (class "Default")
      (node (ref "U2") (pin "9") (pinfunction "IO0_5_9") (pintype "bidirectional"))
    )
    (net (code "57") (name "unconnected-(U2-IO0_6-Pad10)") (class "Default")
      (node (ref "U2") (pin "10") (pinfunction "IO0_6_10") (pintype "bidirectional"))
    )
    (net (code "58") (name "unconnected-(U2-IO0_7-Pad11)") (class "Default")
      (node (ref "U2") (pin "11") (pinfunction "IO0_7_11") (pintype "bidirectional"))
    )
    (net (code "59") (name "unconnected-(U2-IO1_0-Pad13)") (class "Default")
      (node (ref "U2") (pin "13") (pinfunction "IO1_0_13") (pintype "bidirectional"))
    )
    (net (code "60") (name "unconnected-(VL1-GPIO-PadG)") (class "Default")
      (node (ref "VL1") (pin "G") (pinfunction "GPIO_G") (pintype "bidirectional"))
    )
    (net (code "61") (name "unconnected-(VL2-GPIO-PadG)") (class "Default")
      (node (ref "VL2") (pin "G") (pinfunction "GPIO_G") (pintype "bidirectional"))
    )
    (net (code "62") (name "unconnected-(VL3-GPIO-PadG)") (class "Default")
      (node (ref "VL3") (pin "G") (pinfunction "GPIO_G") (pintype "bidirectional"))
    )
    (net (code "63") (name "unconnected-(VL4-GPIO-PadG)") (class "Default")
      (node (ref "VL4") (pin "G") (pinfunction "GPIO_G") (pintype "bidirectional"))
    )
    (net (code "64") (name "unconnected-(VL5-GPIO-PadG)") (class "Default")
      (node (ref "VL5") (pin "G") (pinfunction "GPIO_G") (pintype "bidirectional"))
    )
    (net (code "65") (name "unconnected-(VL6-GPIO-PadG)") (class "Default")
      (node (ref "VL6") (pin "G") (pinfunction "GPIO_G") (pintype "bidirectional"))
    )
    (net (code "66") (name "unconnected-(VL7-GPIO-PadG)") (class "Default")
      (node (ref "VL7") (pin "G") (pinfunction "GPIO_G") (pintype "bidirectional"))
    )
    (net (code "67") (name "unconnected-(VL8-GPIO-PadG)") (class "Default")
      (node (ref "VL8") (pin "G") (pinfunction "GPIO_G") (pintype "bidirectional"))
    )
    (net (code "68") (name "unconnected-(VL9-GPIO-PadG)") (class "Default")
      (node (ref "VL9") (pin "G") (pinfunction "GPIO_G") (pintype "bidirectional"))
    )
    (net (code "69") (name "unconnected-(VL10-GPIO-PadG)") (class "Default")
      (node (ref "VL10") (pin "G") (pinfunction "GPIO_G") (pintype "bidirectional"))
    )
    (net (code "70") (name "unconnected-(VL11-GPIO-PadG)") (class "Default")
      (node (ref "VL11") (pin "G") (pinfunction "GPIO_G") (pintype "bidirectional"))
    )
    (net (code "71") (name "unconnected-(VL12-GPIO-PadG)") (class "Default")
      (node (ref "VL12") (pin "G") (pinfunction "GPIO_G") (pintype "bidirectional"))
    )
  )
)
